# IR_LED.net
KiCad netlist of a schematic drawn in Altium Designer
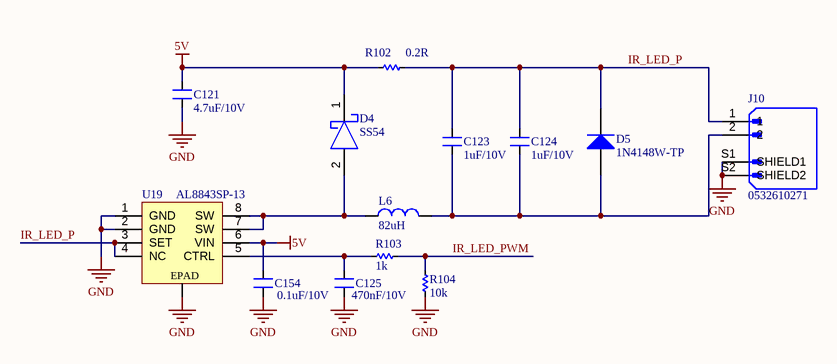
[diagram p0: IR_LED.SchDoc]

(export (version "E")
  (design (tool "Eeschema 10.0.6"))
  (components
    (comp (ref "C121")
      (value "4.7uF/10V")
      (footprint "CAP_C_1608X80")
      (libsource (lib "EXP_HW_V3") (part "Capacitors"))
    )
    (comp (ref "C123")
      (value "1uF/10V")
      (footprint "CAP_C_1608X80")
      (libsource (lib "EXP_HW_V3") (part "Capacitors"))
    )
    (comp (ref "C124")
      (value "1uF/10V")
      (footprint "CAP_C_1608X80")
      (libsource (lib "EXP_HW_V3") (part "Capacitors"))
    )
    (comp (ref "C125")
      (value "470nF/10V")
      (footprint "CAP_C_1608X80")
      (libsource (lib "EXP_HW_V3") (part "Capacitors"))
    )
    (comp (ref "C154")
      (value "0.1uF/10V")
      (footprint "CAP_C_1608X80")
      (libsource (lib "EXP_HW_V3") (part "Capacitors"))
    )
    (comp (ref "D4")
      (value "SS54")
      (footprint "DO214-AC-SMA")
      (description "DIODE SCHOTTKY 60V 3A DO214AA")
      (libsource (lib "EXP_HW_V3") (part "SS54"))
    )
    (comp (ref "D5")
      (value "1N4148W-TP")
      (footprint "SOD-123")
      (description "DIODE GEN PURP 100V 300MA SOD123")
      (fields (field (name "MPN") "1N4148W-7-F") (field (name "MFR") "Diodes Incorporated"))
      (libsource (lib "EXP_HW_V3") (part "1N4148-W-7"))
    )
    (comp (ref "J10")
      (value "0532610271")
      (footprint "0532610271")
      (description "CONN HEADER SMD R/A 2POS 1.25MM")
      (libsource (lib "EXP_HW_V3") (part "CONN_SMD_02"))
    )
    (comp (ref "L6")
      (value "82uH")
      (footprint "L-SMD-M-4.8x4.8x2.8mm")
      (description "SRR4828A-820M")
      (fields
        (field (name "PARTNO") "78477010")
        (field (name "MANUFACTURER") "Wurth Elektronik")
        (field (name "CREATED BY") "Baojun Chen")
      )
      (libsource (lib "EXP_HW_V3") (part "L-SMD-1"))
    )
    (comp (ref "R102")
      (value "0.2R")
      (footprint "RES_C_3216X70")
      (description "RES 0.2 OHM 1% 1W 1206")
      (fields
        (field (name "MANUFACTURER") "Generic Components")
        (field (name "PUBLISHER") "Altium Hobart Technology Centre")
      )
      (libsource (lib "Library") (part "Res-SMD"))
    )
    (comp (ref "R103")
      (value "1k")
      (footprint "RES_C_1608X60")
      (description "SMD")
      (fields
        (field (name "MANUFACTURER") "Generic Components")
        (field (name "PUBLISHER") "Altium Hobart Technology Centre")
      )
      (libsource (lib "EXP_HW_V3") (part "Res SMD"))
    )
    (comp (ref "R104")
      (value "10k")
      (footprint "RES_C_1608X60")
      (description "SMD")
      (fields
        (field (name "MANUFACTURER") "Generic Components")
        (field (name "PUBLISHER") "Altium Hobart Technology Centre")
      )
      (libsource (lib "EXP_HW_V3") (part "Res SMD"))
    )
    (comp (ref "U19")
      (value "AL8843SP-13")
      (footprint "SO8_EPAD")
      (description "IC LED DRIVER RGLTR PWM 3A 8SO")
      (libsource (lib "EXP_HW_V3") (part "AL8843SP-13"))
    )
  )
  (nets
    (net (code "1") (name "/IR_LED_P") (class "Default")
      (node (ref "C123") (pin "2") (pinfunction "2_2") (pintype "passive"))
      (node (ref "C124") (pin "2") (pinfunction "2_2") (pintype "passive"))
      (node (ref "D5") (pin "2") (pinfunction "K_2") (pintype "passive"))
      (node (ref "J10") (pin "1") (pinfunction "1_1") (pintype "passive"))
      (node (ref "R102") (pin "1") (pinfunction "1_1") (pintype "passive"))
      (node (ref "U19") (pin "3") (pinfunction "SET_3") (pintype "passive"))
      (node (ref "U19") (pin "4") (pinfunction "NC_4") (pintype "passive"))
    )
    (net (code "2") (name "/IR_LED_PWM") (class "Default")
      (node (ref "R103") (pin "2") (pinfunction "2_2") (pintype "passive"))
      (node (ref "R104") (pin "2") (pinfunction "2_2") (pintype "passive"))
    )
    (net (code "3") (name "5V") (class "Default")
      (node (ref "C121") (pin "2") (pinfunction "2_2") (pintype "passive"))
      (node (ref "C154") (pin "2") (pinfunction "2_2") (pintype "passive"))
      (node (ref "D4") (pin "1") (pinfunction "1_1") (pintype "passive"))
      (node (ref "R102") (pin "2") (pinfunction "2_2") (pintype "passive"))
      (node (ref "U19") (pin "6") (pinfunction "VIN_6") (pintype "passive"))
    )
    (net (code "4") (name "GND") (class "Default")
      (node (ref "C121") (pin "1") (pinfunction "1_1") (pintype "passive"))
      (node (ref "C125") (pin "1") (pinfunction "1_1") (pintype "passive"))
      (node (ref "C154") (pin "1") (pinfunction "1_1") (pintype "passive"))
      (node (ref "J10") (pin "S1") (pinfunction "SHIELD1_S1") (pintype "passive"))
      (node (ref "J10") (pin "S2") (pinfunction "SHIELD2_S2") (pintype "passive"))
      (node (ref "R104") (pin "1") (pinfunction "1_1") (pintype "passive"))
      (node (ref "U19") (pin "1") (pinfunction "GND_1") (pintype "passive"))
      (node (ref "U19") (pin "2") (pinfunction "GND_2") (pintype "passive"))
      (node (ref "U19") (pin "EPAD") (pinfunction "EPAD_EPAD") (pintype "passive"))
    )
    (net (code "5") (name "Net-(D4-Pad2)") (class "Default")
      (node (ref "D4") (pin "2") (pinfunction "2_2") (pintype "passive"))
      (node (ref "L6") (pin "1") (pinfunction "1_1") (pintype "passive"))
      (node (ref "U19") (pin "7") (pinfunction "SW_7") (pintype "passive"))
      (node (ref "U19") (pin "8") (pinfunction "SW_8") (pintype "passive"))
    )
    (net (code "6") (name "Net-(D5-A)") (class "Default")
      (node (ref "C123") (pin "1") (pinfunction "1_1") (pintype "passive"))
      (node (ref "C124") (pin "1") (pinfunction "1_1") (pintype "passive"))
      (node (ref "D5") (pin "1") (pinfunction "A_1") (pintype "passive"))
      (node (ref "J10") (pin "2") (pinfunction "2_2") (pintype "passive"))
      (node (ref "L6") (pin "2") (pinfunction "2_2") (pintype "passive"))
    )
    (net (code "7") (name "Net-(U19-CTRL)") (class "Default")
      (node (ref "C125") (pin "2") (pinfunction "2_2") (pintype "passive"))
      (node (ref "R103") (pin "1") (pinfunction "1_1") (pintype "passive"))
      (node (ref "U19") (pin "5") (pinfunction "CTRL_5") (pintype "passive"))
    )
  )
)
